# Schema_PcbBspd_NF.net
KiCad netlist of a schematic drawn in EAGLE
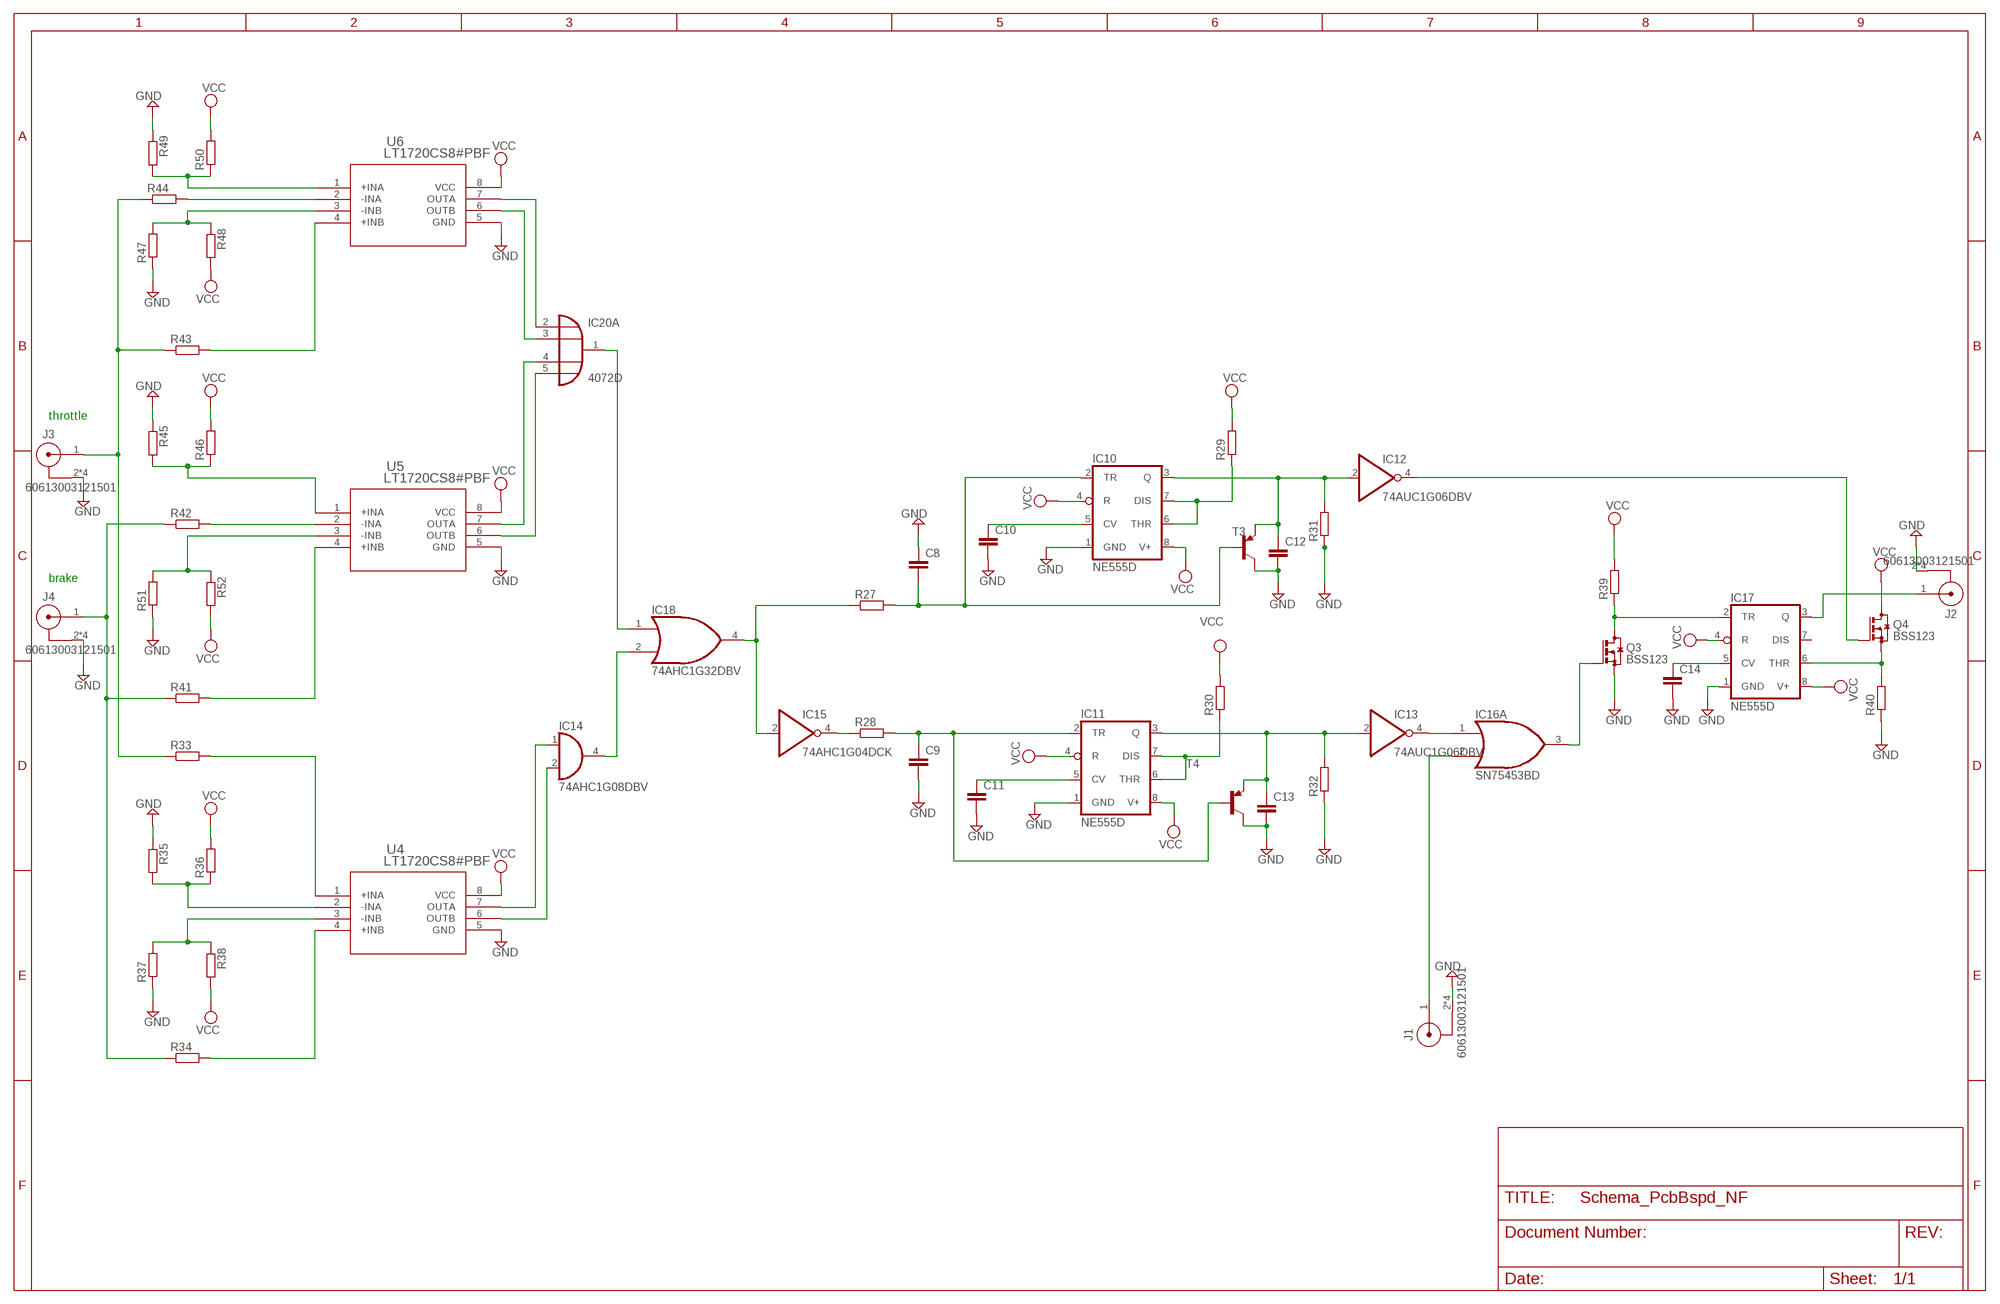
[diagram p0: schematic, sheet 1]

(export (version "E")
  (design (tool "Eeschema 10.0.6"))
  (components
    (comp (ref "C8")
      (value "C2,5-3")
      (footprint "eagle-import:C2.5-3")
      (libsource (lib "eagle-import") (part "C2,5-3"))
    )
    (comp (ref "C9")
      (value "C2,5-3")
      (footprint "eagle-import:C2.5-3")
      (libsource (lib "eagle-import") (part "C2,5-3"))
    )
    (comp (ref "C10")
      (value "C2,5-3")
      (footprint "eagle-import:C2.5-3")
      (libsource (lib "eagle-import") (part "C2,5-3"))
    )
    (comp (ref "C11")
      (value "C2,5-3")
      (footprint "eagle-import:C2.5-3")
      (libsource (lib "eagle-import") (part "C2,5-3"))
    )
    (comp (ref "C12")
      (value "C2,5-3")
      (footprint "eagle-import:C2.5-3")
      (libsource (lib "eagle-import") (part "C2,5-3"))
    )
    (comp (ref "C13")
      (value "C2,5-3")
      (footprint "eagle-import:C2.5-3")
      (libsource (lib "eagle-import") (part "C2,5-3"))
    )
    (comp (ref "C14")
      (value "C2,5-3")
      (footprint "eagle-import:C2.5-3")
      (libsource (lib "eagle-import") (part "C2,5-3"))
    )
    (comp (ref "IC10")
      (value "NE555D")
      (footprint "eagle-import:SO08")
      (libsource (lib "eagle-import") (part "555DNE"))
    )
    (comp (ref "IC11")
      (value "NE555D")
      (footprint "eagle-import:SO08")
      (libsource (lib "eagle-import") (part "555DNE"))
    )
    (comp (ref "IC12")
      (value "74AUC1G06DBV")
      (footprint "eagle-import:SOT23-5")
      (libsource (lib "eagle-import") (part "741G06DBVAUC"))
    )
    (comp (ref "IC13")
      (value "74AUC1G06DBV")
      (footprint "eagle-import:SOT23-5")
      (libsource (lib "eagle-import") (part "741G06DBVAUC"))
    )
    (comp (ref "IC14")
      (value "74AHC1G08DBV")
      (footprint "eagle-import:SOT23-5")
      (libsource (lib "eagle-import") (part "741G08DBVAHC"))
    )
    (comp (ref "IC15")
      (value "74AHC1G04DCK")
      (footprint "eagle-import:SC70-5")
      (libsource (lib "eagle-import") (part "741G04DCKAHC"))
    )
    (comp (ref "IC16")
      (value "SN75453BD")
      (footprint "eagle-import:D_R-PDSO-G8")
      (libsource (lib "eagle-import") (part "SN75453BD"))
    )
    (comp (ref "IC17")
      (value "NE555D")
      (footprint "eagle-import:SO08")
      (libsource (lib "eagle-import") (part "555DNE"))
    )
    (comp (ref "IC18")
      (value "74AHC1G32DBV")
      (footprint "eagle-import:SOT23-5")
      (libsource (lib "eagle-import") (part "741G32DBVAHC"))
    )
    (comp (ref "IC20")
      (value "4072D")
      (footprint "eagle-import:SO14")
      (libsource (lib "eagle-import") (part "4072D"))
    )
    (comp (ref "J1")
      (value "60613003121501")
      (footprint "eagle-import:60613003121501")
      (fields (field (name "MF") "Wurth Elektronik"))
      (libsource (lib "eagle-import") (part "60613003121501"))
    )
    (comp (ref "J2")
      (value "60613003121501")
      (footprint "eagle-import:60613003121501")
      (fields (field (name "MF") "Wurth Elektronik"))
      (libsource (lib "eagle-import") (part "60613003121501"))
    )
    (comp (ref "J3")
      (value "60613003121501")
      (footprint "eagle-import:60613003121501")
      (fields (field (name "MF") "Wurth Elektronik"))
      (libsource (lib "eagle-import") (part "60613003121501"))
    )
    (comp (ref "J4")
      (value "60613003121501")
      (footprint "eagle-import:60613003121501")
      (fields (field (name "MF") "Wurth Elektronik"))
      (libsource (lib "eagle-import") (part "60613003121501"))
    )
    (comp (ref "Q3")
      (value "BSS123")
      (footprint "eagle-import:SOT23")
      (libsource (lib "eagle-import") (part "BSS123"))
    )
    (comp (ref "Q4")
      (value "BSS123")
      (footprint "eagle-import:SOT23")
      (libsource (lib "eagle-import") (part "BSS123"))
    )
    (comp (ref "R27")
      (value "R-EU_R0805")
      (footprint "eagle-import:R0805")
      (libsource (lib "eagle-import") (part "R-EU_R0805"))
    )
    (comp (ref "R28")
      (value "R-EU_R0805")
      (footprint "eagle-import:R0805")
      (libsource (lib "eagle-import") (part "R-EU_R0805"))
    )
    (comp (ref "R29")
      (value "R-EU_R0805")
      (footprint "eagle-import:R0805")
      (libsource (lib "eagle-import") (part "R-EU_R0805"))
    )
    (comp (ref "R30")
      (value "R-EU_R0805")
      (footprint "eagle-import:R0805")
      (libsource (lib "eagle-import") (part "R-EU_R0805"))
    )
    (comp (ref "R31")
      (value "R-EU_R0805")
      (footprint "eagle-import:R0805")
      (libsource (lib "eagle-import") (part "R-EU_R0805"))
    )
    (comp (ref "R32")
      (value "R-EU_R0805")
      (footprint "eagle-import:R0805")
      (libsource (lib "eagle-import") (part "R-EU_R0805"))
    )
    (comp (ref "R33")
      (value "R-EU_R0805")
      (footprint "eagle-import:R0805")
      (libsource (lib "eagle-import") (part "R-EU_R0805"))
    )
    (comp (ref "R34")
      (value "R-EU_R0805")
      (footprint "eagle-import:R0805")
      (libsource (lib "eagle-import") (part "R-EU_R0805"))
    )
    (comp (ref "R35")
      (value "R-EU_R0805")
      (footprint "eagle-import:R0805")
      (libsource (lib "eagle-import") (part "R-EU_R0805"))
    )
    (comp (ref "R36")
      (value "R-EU_R0805")
      (footprint "eagle-import:R0805")
      (libsource (lib "eagle-import") (part "R-EU_R0805"))
    )
    (comp (ref "R37")
      (value "R-EU_R0805")
      (footprint "eagle-import:R0805")
      (libsource (lib "eagle-import") (part "R-EU_R0805"))
    )
    (comp (ref "R38")
      (value "R-EU_R0805")
      (footprint "eagle-import:R0805")
      (libsource (lib "eagle-import") (part "R-EU_R0805"))
    )
    (comp (ref "R39")
      (value "R-EU_R0805")
      (footprint "eagle-import:R0805")
      (libsource (lib "eagle-import") (part "R-EU_R0805"))
    )
    (comp (ref "R40")
      (value "R-EU_R0805")
      (footprint "eagle-import:R0805")
      (libsource (lib "eagle-import") (part "R-EU_R0805"))
    )
    (comp (ref "R41")
      (value "R-EU_R0805")
      (footprint "eagle-import:R0805")
      (libsource (lib "eagle-import") (part "R-EU_R0805"))
    )
    (comp (ref "R42")
      (value "R-EU_R0805")
      (footprint "eagle-import:R0805")
      (libsource (lib "eagle-import") (part "R-EU_R0805"))
    )
    (comp (ref "R43")
      (value "R-EU_R0805")
      (footprint "eagle-import:R0805")
      (libsource (lib "eagle-import") (part "R-EU_R0805"))
    )
    (comp (ref "R44")
      (value "R-EU_R0805")
      (footprint "eagle-import:R0805")
      (libsource (lib "eagle-import") (part "R-EU_R0805"))
    )
    (comp (ref "R45")
      (value "R-EU_R0805")
      (footprint "eagle-import:R0805")
      (libsource (lib "eagle-import") (part "R-EU_R0805"))
    )
    (comp (ref "R46")
      (value "R-EU_R0805")
      (footprint "eagle-import:R0805")
      (libsource (lib "eagle-import") (part "R-EU_R0805"))
    )
    (comp (ref "R47")
      (value "R-EU_R0805")
      (footprint "eagle-import:R0805")
      (libsource (lib "eagle-import") (part "R-EU_R0805"))
    )
    (comp (ref "R48")
      (value "R-EU_R0805")
      (footprint "eagle-import:R0805")
      (libsource (lib "eagle-import") (part "R-EU_R0805"))
    )
    (comp (ref "R49")
      (value "R-EU_R0805")
      (footprint "eagle-import:R0805")
      (libsource (lib "eagle-import") (part "R-EU_R0805"))
    )
    (comp (ref "R50")
      (value "R-EU_R0805")
      (footprint "eagle-import:R0805")
      (libsource (lib "eagle-import") (part "R-EU_R0805"))
    )
    (comp (ref "R51")
      (value "R-EU_R0805")
      (footprint "eagle-import:R0805")
      (libsource (lib "eagle-import") (part "R-EU_R0805"))
    )
    (comp (ref "R52")
      (value "R-EU_R0805")
      (footprint "eagle-import:R0805")
      (libsource (lib "eagle-import") (part "R-EU_R0805"))
    )
    (comp (ref "T3")
      (value "BC857A-PNP-SOT23-BEC")
      (footprint "eagle-import:SOT23-BEC")
      (libsource (lib "eagle-import") (part "-PNP-SOT23-BECBC857A"))
    )
    (comp (ref "T4")
      (value "BC857A-PNP-SOT23-BEC")
      (footprint "eagle-import:SOT23-BEC")
      (libsource (lib "eagle-import") (part "-PNP-SOT23-BECBC857A"))
    )
    (comp (ref "U4")
      (value "LT1720CS8#PBF")
      (footprint "eagle-import:SO-8_S")
      (fields (field (name "MF") "Analog Devices"))
      (libsource (lib "eagle-import") (part "LT1720CS8#PBF"))
    )
    (comp (ref "U5")
      (value "LT1720CS8#PBF")
      (footprint "eagle-import:SO-8_S")
      (fields (field (name "MF") "Analog Devices"))
      (libsource (lib "eagle-import") (part "LT1720CS8#PBF"))
    )
    (comp (ref "U6")
      (value "LT1720CS8#PBF")
      (footprint "eagle-import:SO-8_S")
      (fields (field (name "MF") "Analog Devices"))
      (libsource (lib "eagle-import") (part "LT1720CS8#PBF"))
    )
  )
  (nets
    (net (code "1") (name "GND") (class "Default")
      (node (ref "C10") (pin "2") (pinfunction "2_2") (pintype "passive"))
      (node (ref "C11") (pin "2") (pinfunction "2_2") (pintype "passive"))
      (node (ref "C12") (pin "2") (pinfunction "2_2") (pintype "passive"))
      (node (ref "C13") (pin "2") (pinfunction "2_2") (pintype "passive"))
      (node (ref "C14") (pin "2") (pinfunction "2_2") (pintype "passive"))
      (node (ref "C8") (pin "1") (pinfunction "1_1") (pintype "passive"))
      (node (ref "C9") (pin "2") (pinfunction "2_2") (pintype "passive"))
      (node (ref "IC10") (pin "1") (pinfunction "GND_1") (pintype "power_in"))
      (node (ref "IC11") (pin "1") (pinfunction "GND_1") (pintype "power_in"))
      (node (ref "IC17") (pin "1") (pinfunction "GND_1") (pintype "power_in"))
      (node (ref "J1") (pin "2") (pinfunction "2_2") (pintype "passive"))
      (node (ref "J1") (pin "3") (pinfunction "2_3") (pintype "passive"))
      (node (ref "J1") (pin "4") (pinfunction "2_4") (pintype "passive"))
      (node (ref "J1") (pin "5") (pinfunction "2_5") (pintype "passive"))
      (node (ref "J2") (pin "2") (pinfunction "2_2") (pintype "passive"))
      (node (ref "J2") (pin "3") (pinfunction "2_3") (pintype "passive"))
      (node (ref "J2") (pin "4") (pinfunction "2_4") (pintype "passive"))
      (node (ref "J2") (pin "5") (pinfunction "2_5") (pintype "passive"))
      (node (ref "J3") (pin "2") (pinfunction "2_2") (pintype "passive"))
      (node (ref "J3") (pin "3") (pinfunction "2_3") (pintype "passive"))
      (node (ref "J3") (pin "4") (pinfunction "2_4") (pintype "passive"))
      (node (ref "J3") (pin "5") (pinfunction "2_5") (pintype "passive"))
      (node (ref "J4") (pin "2") (pinfunction "2_2") (pintype "passive"))
      (node (ref "J4") (pin "3") (pinfunction "2_3") (pintype "passive"))
      (node (ref "J4") (pin "4") (pinfunction "2_4") (pintype "passive"))
      (node (ref "J4") (pin "5") (pinfunction "2_5") (pintype "passive"))
      (node (ref "Q3") (pin "2") (pinfunction "S_2") (pintype "passive"))
      (node (ref "R31") (pin "1") (pinfunction "1_1") (pintype "passive"))
      (node (ref "R32") (pin "1") (pinfunction "1_1") (pintype "passive"))
      (node (ref "R35") (pin "1") (pinfunction "1_1") (pintype "passive"))
      (node (ref "R37") (pin "1") (pinfunction "1_1") (pintype "passive"))
      (node (ref "R40") (pin "1") (pinfunction "1_1") (pintype "passive"))
      (node (ref "R45") (pin "1") (pinfunction "1_1") (pintype "passive"))
      (node (ref "R47") (pin "1") (pinfunction "1_1") (pintype "passive"))
      (node (ref "R49") (pin "1") (pinfunction "1_1") (pintype "passive"))
      (node (ref "R51") (pin "1") (pinfunction "1_1") (pintype "passive"))
      (node (ref "T3") (pin "C") (pinfunction "C_C") (pintype "passive"))
      (node (ref "T4") (pin "C") (pinfunction "C_C") (pintype "passive"))
      (node (ref "U4") (pin "5") (pinfunction "GND_5") (pintype "power_in"))
      (node (ref "U5") (pin "5") (pinfunction "GND_5") (pintype "power_in"))
      (node (ref "U6") (pin "5") (pinfunction "GND_5") (pintype "power_in"))
    )
    (net (code "2") (name "Net-(IC10-CV)") (class "Default")
      (node (ref "C10") (pin "1") (pinfunction "1_1") (pintype "passive"))
      (node (ref "IC10") (pin "5") (pinfunction "CV_5") (pintype "input"))
    )
    (net (code "3") (name "Net-(IC10-DIS)") (class "Default")
      (node (ref "IC10") (pin "6") (pinfunction "THR_6") (pintype "input"))
      (node (ref "IC10") (pin "7") (pinfunction "DIS_7") (pintype "input"))
      (node (ref "R29") (pin "1") (pinfunction "1_1") (pintype "passive"))
    )
    (net (code "4") (name "Net-(IC10-Q)") (class "Default")
      (node (ref "C12") (pin "1") (pinfunction "1_1") (pintype "passive"))
      (node (ref "IC10") (pin "3") (pinfunction "Q_3") (pintype "output"))
      (node (ref "IC12") (pin "2") (pinfunction "I_2") (pintype "input"))
      (node (ref "R31") (pin "2") (pinfunction "2_2") (pintype "passive"))
      (node (ref "T3") (pin "E") (pinfunction "E_E") (pintype "passive"))
    )
    (net (code "5") (name "Net-(IC10-TR)") (class "Default")
      (node (ref "C8") (pin "2") (pinfunction "2_2") (pintype "passive"))
      (node (ref "IC10") (pin "2") (pinfunction "TR_2") (pintype "input"))
      (node (ref "R27") (pin "2") (pinfunction "2_2") (pintype "passive"))
      (node (ref "T3") (pin "B") (pinfunction "B_B") (pintype "passive"))
    )
    (net (code "6") (name "Net-(IC11-CV)") (class "Default")
      (node (ref "C11") (pin "1") (pinfunction "1_1") (pintype "passive"))
      (node (ref "IC11") (pin "5") (pinfunction "CV_5") (pintype "input"))
    )
    (net (code "7") (name "Net-(IC11-DIS)") (class "Default")
      (node (ref "IC11") (pin "6") (pinfunction "THR_6") (pintype "input"))
      (node (ref "IC11") (pin "7") (pinfunction "DIS_7") (pintype "input"))
      (node (ref "R30") (pin "1") (pinfunction "1_1") (pintype "passive"))
    )
    (net (code "8") (name "Net-(IC11-Q)") (class "Default")
      (node (ref "C13") (pin "1") (pinfunction "1_1") (pintype "passive"))
      (node (ref "IC11") (pin "3") (pinfunction "Q_3") (pintype "output"))
      (node (ref "IC13") (pin "2") (pinfunction "I_2") (pintype "input"))
      (node (ref "R32") (pin "2") (pinfunction "2_2") (pintype "passive"))
      (node (ref "T4") (pin "E") (pinfunction "E_E") (pintype "passive"))
    )
    (net (code "9") (name "Net-(IC11-TR)") (class "Default")
      (node (ref "C9") (pin "1") (pinfunction "1_1") (pintype "passive"))
      (node (ref "IC11") (pin "2") (pinfunction "TR_2") (pintype "input"))
      (node (ref "R28") (pin "2") (pinfunction "2_2") (pintype "passive"))
      (node (ref "T4") (pin "B") (pinfunction "B_B") (pintype "passive"))
    )
    (net (code "10") (name "Net-(IC12A-O)") (class "Default")
      (node (ref "IC12") (pin "4") (pinfunction "O_4") (pintype "open_collector"))
      (node (ref "Q4") (pin "1") (pinfunction "G_1") (pintype "passive"))
    )
    (net (code "11") (name "Net-(IC13A-O)") (class "Default")
      (node (ref "IC13") (pin "4") (pinfunction "O_4") (pintype "open_collector"))
      (node (ref "IC16") (pin "1") (pinfunction "I0_1") (pintype "input"))
    )
    (net (code "12") (name "Net-(IC14A-I0)") (class "Default")
      (node (ref "IC14") (pin "1") (pinfunction "I0_1") (pintype "input"))
      (node (ref "U4") (pin "7") (pinfunction "OUTA_7") (pintype "output"))
    )
    (net (code "13") (name "Net-(IC14A-I1)") (class "Default")
      (node (ref "IC14") (pin "2") (pinfunction "I1_2") (pintype "input"))
      (node (ref "U4") (pin "6") (pinfunction "OUTB_6") (pintype "output"))
    )
    (net (code "14") (name "Net-(IC14A-O)") (class "Default")
      (node (ref "IC14") (pin "4") (pinfunction "O_4") (pintype "output"))
      (node (ref "IC18") (pin "2") (pinfunction "I1_2") (pintype "input"))
    )
    (net (code "15") (name "Net-(IC15A-I)") (class "Default")
      (node (ref "IC15") (pin "2") (pinfunction "I_2") (pintype "input"))
      (node (ref "IC18") (pin "4") (pinfunction "O_4") (pintype "output"))
      (node (ref "R27") (pin "1") (pinfunction "1_1") (pintype "passive"))
    )
    (net (code "16") (name "Net-(IC15A-O)") (class "Default")
      (node (ref "IC15") (pin "4") (pinfunction "O_4") (pintype "output"))
      (node (ref "R28") (pin "1") (pinfunction "1_1") (pintype "passive"))
    )
    (net (code "17") (name "Net-(IC16A-I1)") (class "Default")
      (node (ref "IC16") (pin "2") (pinfunction "I1_2") (pintype "input"))
      (node (ref "J1") (pin "1") (pinfunction "1_1") (pintype "passive"))
    )
    (net (code "18") (name "Net-(IC16A-O)") (class "Default")
      (node (ref "IC16") (pin "3") (pinfunction "O_3") (pintype "output"))
      (node (ref "Q3") (pin "1") (pinfunction "G_1") (pintype "passive"))
    )
    (net (code "19") (name "Net-(IC17-CV)") (class "Default")
      (node (ref "C14") (pin "1") (pinfunction "1_1") (pintype "passive"))
      (node (ref "IC17") (pin "5") (pinfunction "CV_5") (pintype "input"))
    )
    (net (code "20") (name "Net-(IC17-Q)") (class "Default")
      (node (ref "IC17") (pin "3") (pinfunction "Q_3") (pintype "output"))
      (node (ref "J2") (pin "1") (pinfunction "1_1") (pintype "passive"))
    )
    (net (code "21") (name "Net-(IC17-THR)") (class "Default")
      (node (ref "IC17") (pin "6") (pinfunction "THR_6") (pintype "input"))
      (node (ref "Q4") (pin "2") (pinfunction "S_2") (pintype "passive"))
      (node (ref "R40") (pin "2") (pinfunction "2_2") (pintype "passive"))
    )
    (net (code "22") (name "Net-(IC17-TR)") (class "Default")
      (node (ref "IC17") (pin "2") (pinfunction "TR_2") (pintype "input"))
      (node (ref "Q3") (pin "3") (pinfunction "D_3") (pintype "passive"))
      (node (ref "R39") (pin "1") (pinfunction "1_1") (pintype "passive"))
    )
    (net (code "23") (name "Net-(IC18A-I0)") (class "Default")
      (node (ref "IC18") (pin "1") (pinfunction "I0_1") (pintype "input"))
      (node (ref "IC20") (pin "1") (pinfunction "O_1") (pintype "output"))
    )
    (net (code "24") (name "Net-(IC20A-I0)") (class "Default")
      (node (ref "IC20") (pin "2") (pinfunction "I0_2") (pintype "input"))
      (node (ref "U6") (pin "7") (pinfunction "OUTA_7") (pintype "output"))
    )
    (net (code "25") (name "Net-(IC20A-I1)") (class "Default")
      (node (ref "IC20") (pin "3") (pinfunction "I1_3") (pintype "input"))
      (node (ref "U6") (pin "6") (pinfunction "OUTB_6") (pintype "output"))
    )
    (net (code "26") (name "Net-(IC20A-I2)") (class "Default")
      (node (ref "IC20") (pin "4") (pinfunction "I2_4") (pintype "input"))
      (node (ref "U5") (pin "7") (pinfunction "OUTA_7") (pintype "output"))
    )
    (net (code "27") (name "Net-(IC20A-I3)") (class "Default")
      (node (ref "IC20") (pin "5") (pinfunction "I3_5") (pintype "input"))
      (node (ref "U5") (pin "6") (pinfunction "OUTB_6") (pintype "output"))
    )
    (net (code "28") (name "Net-(J3-Pad1)") (class "Default")
      (node (ref "J3") (pin "1") (pinfunction "1_1") (pintype "passive"))
      (node (ref "R33") (pin "1") (pinfunction "1_1") (pintype "passive"))
      (node (ref "R43") (pin "1") (pinfunction "1_1") (pintype "passive"))
      (node (ref "R44") (pin "1") (pinfunction "1_1") (pintype "passive"))
    )
    (net (code "29") (name "Net-(J4-Pad1)") (class "Default")
      (node (ref "J4") (pin "1") (pinfunction "1_1") (pintype "passive"))
      (node (ref "R34") (pin "1") (pinfunction "1_1") (pintype "passive"))
      (node (ref "R41") (pin "1") (pinfunction "1_1") (pintype "passive"))
      (node (ref "R42") (pin "1") (pinfunction "1_1") (pintype "passive"))
    )
    (net (code "30") (name "Net-(U4-+INA)") (class "Default")
      (node (ref "R33") (pin "2") (pinfunction "2_2") (pintype "passive"))
      (node (ref "U4") (pin "1") (pinfunction "+INA_1") (pintype "input"))
    )
    (net (code "31") (name "Net-(U4-+INB)") (class "Default")
      (node (ref "R34") (pin "2") (pinfunction "2_2") (pintype "passive"))
      (node (ref "U4") (pin "4") (pinfunction "+INB_4") (pintype "input"))
    )
    (net (code "32") (name "Net-(U4--INA)") (class "Default")
      (node (ref "R35") (pin "2") (pinfunction "2_2") (pintype "passive"))
      (node (ref "R36") (pin "1") (pinfunction "1_1") (pintype "passive"))
      (node (ref "U4") (pin "2") (pinfunction "-INA_2") (pintype "input"))
    )
    (net (code "33") (name "Net-(U4--INB)") (class "Default")
      (node (ref "R37") (pin "2") (pinfunction "2_2") (pintype "passive"))
      (node (ref "R38") (pin "1") (pinfunction "1_1") (pintype "passive"))
      (node (ref "U4") (pin "3") (pinfunction "-INB_3") (pintype "input"))
    )
    (net (code "34") (name "Net-(U5-+INA)") (class "Default")
      (node (ref "R45") (pin "2") (pinfunction "2_2") (pintype "passive"))
      (node (ref "R46") (pin "1") (pinfunction "1_1") (pintype "passive"))
      (node (ref "U5") (pin "1") (pinfunction "+INA_1") (pintype "input"))
    )
    (net (code "35") (name "Net-(U5-+INB)") (class "Default")
      (node (ref "R41") (pin "2") (pinfunction "2_2") (pintype "passive"))
      (node (ref "U5") (pin "4") (pinfunction "+INB_4") (pintype "input"))
    )
    (net (code "36") (name "Net-(U5--INA)") (class "Default")
      (node (ref "R42") (pin "2") (pinfunction "2_2") (pintype "passive"))
      (node (ref "U5") (pin "2") (pinfunction "-INA_2") (pintype "input"))
    )
    (net (code "37") (name "Net-(U5--INB)") (class "Default")
      (node (ref "R51") (pin "2") (pinfunction "2_2") (pintype "passive"))
      (node (ref "R52") (pin "1") (pinfunction "1_1") (pintype "passive"))
      (node (ref "U5") (pin "3") (pinfunction "-INB_3") (pintype "input"))
    )
    (net (code "38") (name "Net-(U6-+INA)") (class "Default")
      (node (ref "R49") (pin "2") (pinfunction "2_2") (pintype "passive"))
      (node (ref "R50") (pin "1") (pinfunction "1_1") (pintype "passive"))
      (node (ref "U6") (pin "1") (pinfunction "+INA_1") (pintype "input"))
    )
    (net (code "39") (name "Net-(U6-+INB)") (class "Default")
      (node (ref "R43") (pin "2") (pinfunction "2_2") (pintype "passive"))
      (node (ref "U6") (pin "4") (pinfunction "+INB_4") (pintype "input"))
    )
    (net (code "40") (name "Net-(U6--INA)") (class "Default")
      (node (ref "R44") (pin "2") (pinfunction "2_2") (pintype "passive"))
      (node (ref "U6") (pin "2") (pinfunction "-INA_2") (pintype "input"))
    )
    (net (code "41") (name "Net-(U6--INB)") (class "Default")
      (node (ref "R47") (pin "2") (pinfunction "2_2") (pintype "passive"))
      (node (ref "R48") (pin "1") (pinfunction "1_1") (pintype "passive"))
      (node (ref "U6") (pin "3") (pinfunction "-INB_3") (pintype "input"))
    )
    (net (code "42") (name "VCC") (class "Default")
      (node (ref "IC10") (pin "4") (pinfunction "R_4") (pintype "input"))
      (node (ref "IC10") (pin "8") (pinfunction "V+_8") (pintype "power_in"))
      (node (ref "IC11") (pin "4") (pinfunction "R_4") (pintype "input"))
      (node (ref "IC11") (pin "8") (pinfunction "V+_8") (pintype "power_in"))
      (node (ref "IC17") (pin "4") (pinfunction "R_4") (pintype "input"))
      (node (ref "IC17") (pin "8") (pinfunction "V+_8") (pintype "power_in"))
      (node (ref "Q4") (pin "3") (pinfunction "D_3") (pintype "passive"))
      (node (ref "R29") (pin "2") (pinfunction "2_2") (pintype "passive"))
      (node (ref "R30") (pin "2") (pinfunction "2_2") (pintype "passive"))
      (node (ref "R36") (pin "2") (pinfunction "2_2") (pintype "passive"))
      (node (ref "R38") (pin "2") (pinfunction "2_2") (pintype "passive"))
      (node (ref "R39") (pin "2") (pinfunction "2_2") (pintype "passive"))
      (node (ref "R46") (pin "2") (pinfunction "2_2") (pintype "passive"))
      (node (ref "R48") (pin "2") (pinfunction "2_2") (pintype "passive"))
      (node (ref "R50") (pin "2") (pinfunction "2_2") (pintype "passive"))
      (node (ref "R52") (pin "2") (pinfunction "2_2") (pintype "passive"))
      (node (ref "U4") (pin "8") (pinfunction "VCC_8") (pintype "power_in"))
      (node (ref "U5") (pin "8") (pinfunction "VCC_8") (pintype "power_in"))
      (node (ref "U6") (pin "8") (pinfunction "VCC_8") (pintype "power_in"))
    )
    (net (code "43") (name "unconnected-(IC17-DIS-Pad7)") (class "Default")
      (node (ref "IC17") (pin "7") (pinfunction "DIS_7") (pintype "input"))
    )
  )
)
